# CarrierBoard_V7.net
KiCad netlist of a schematic drawn in EAGLE
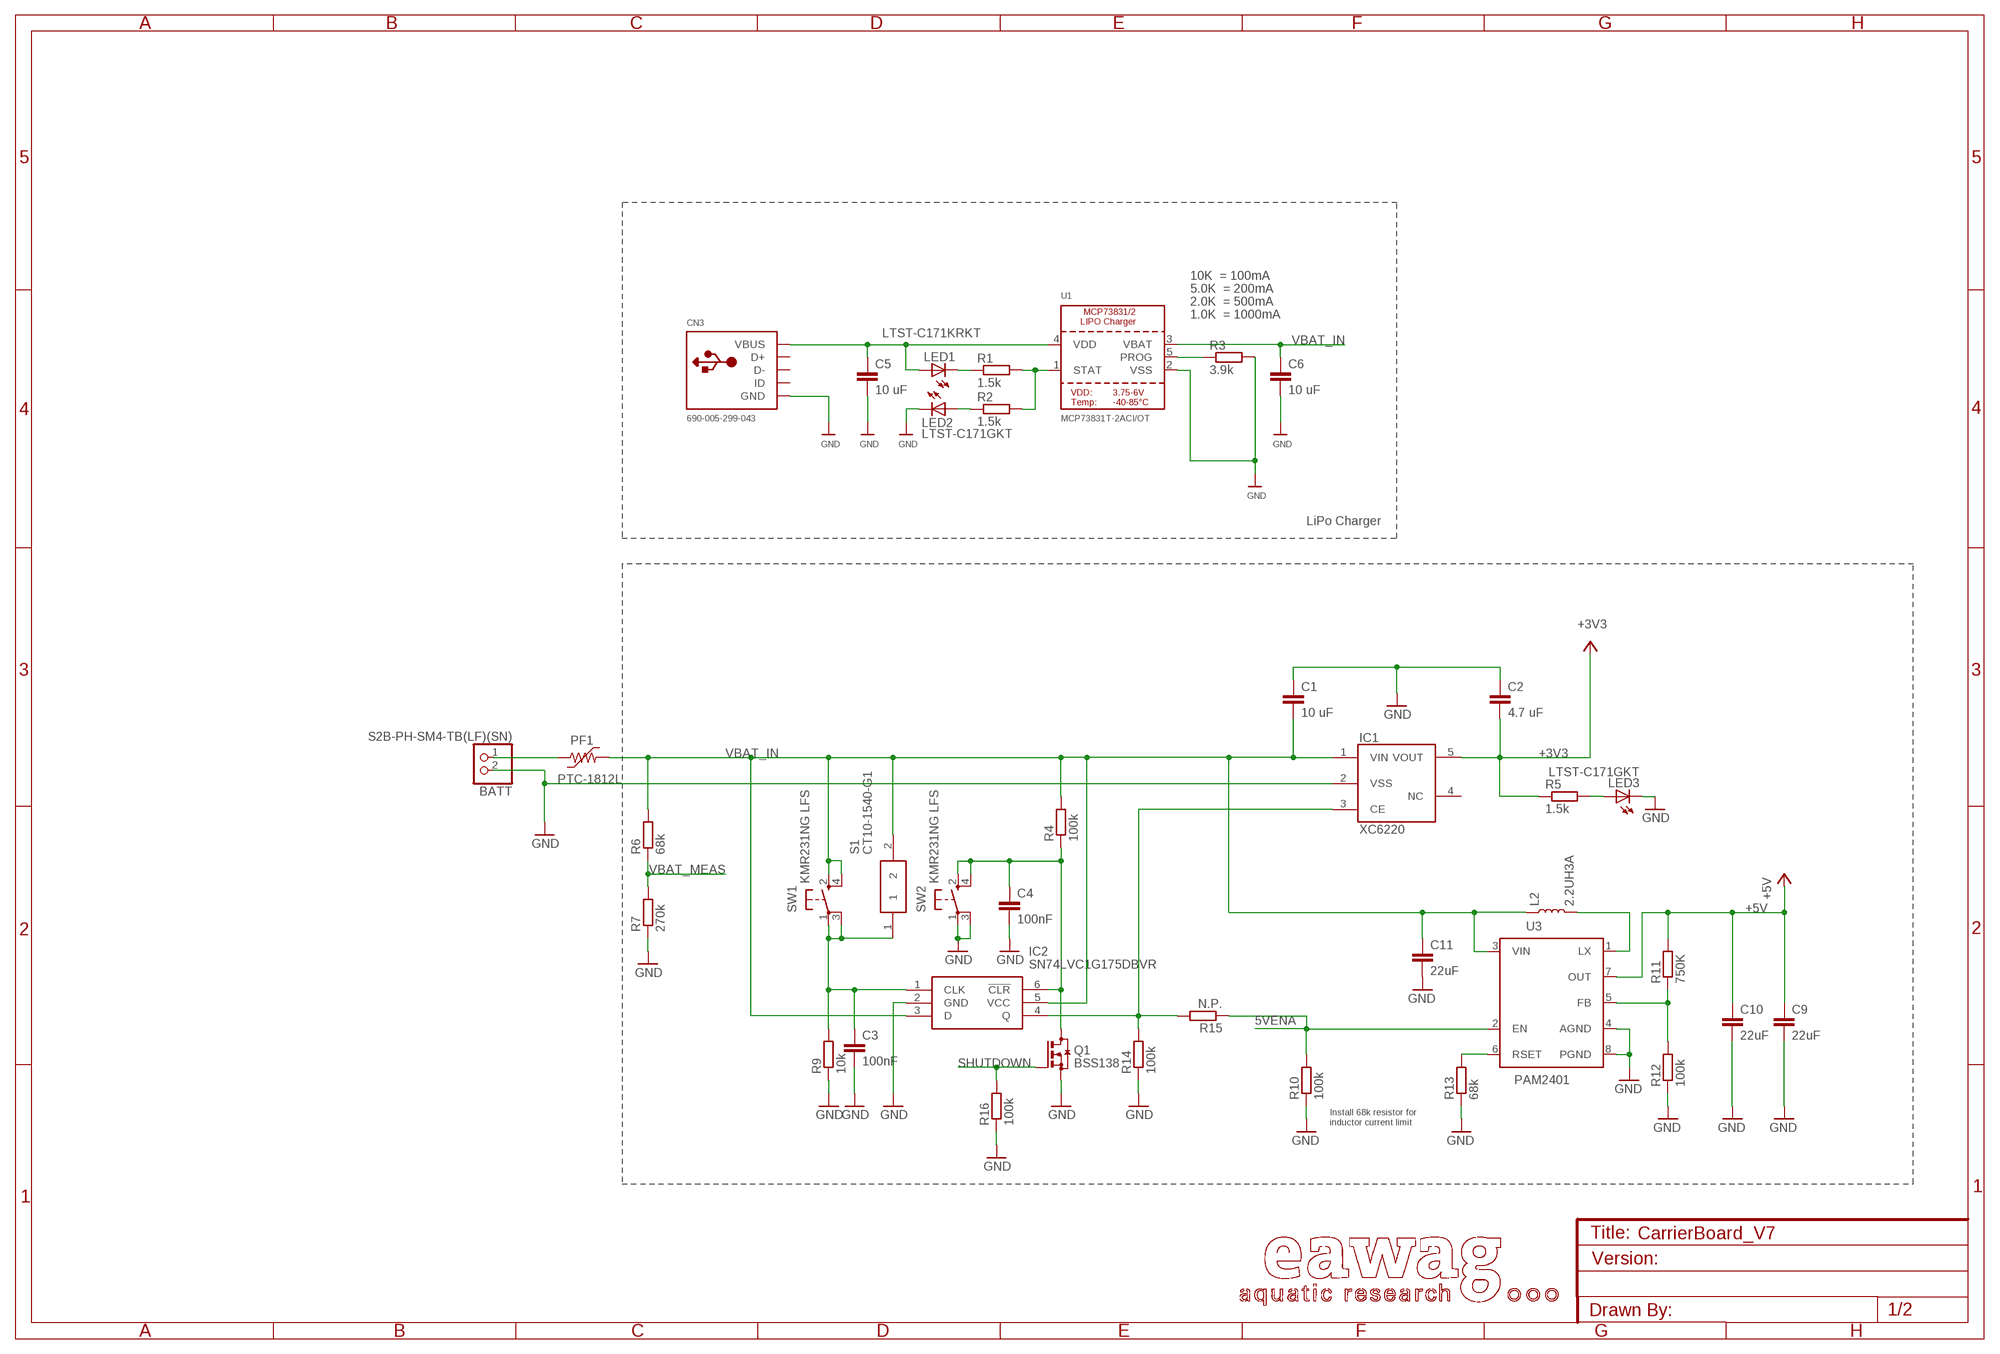
[diagram p0: schematic, sheet 1]
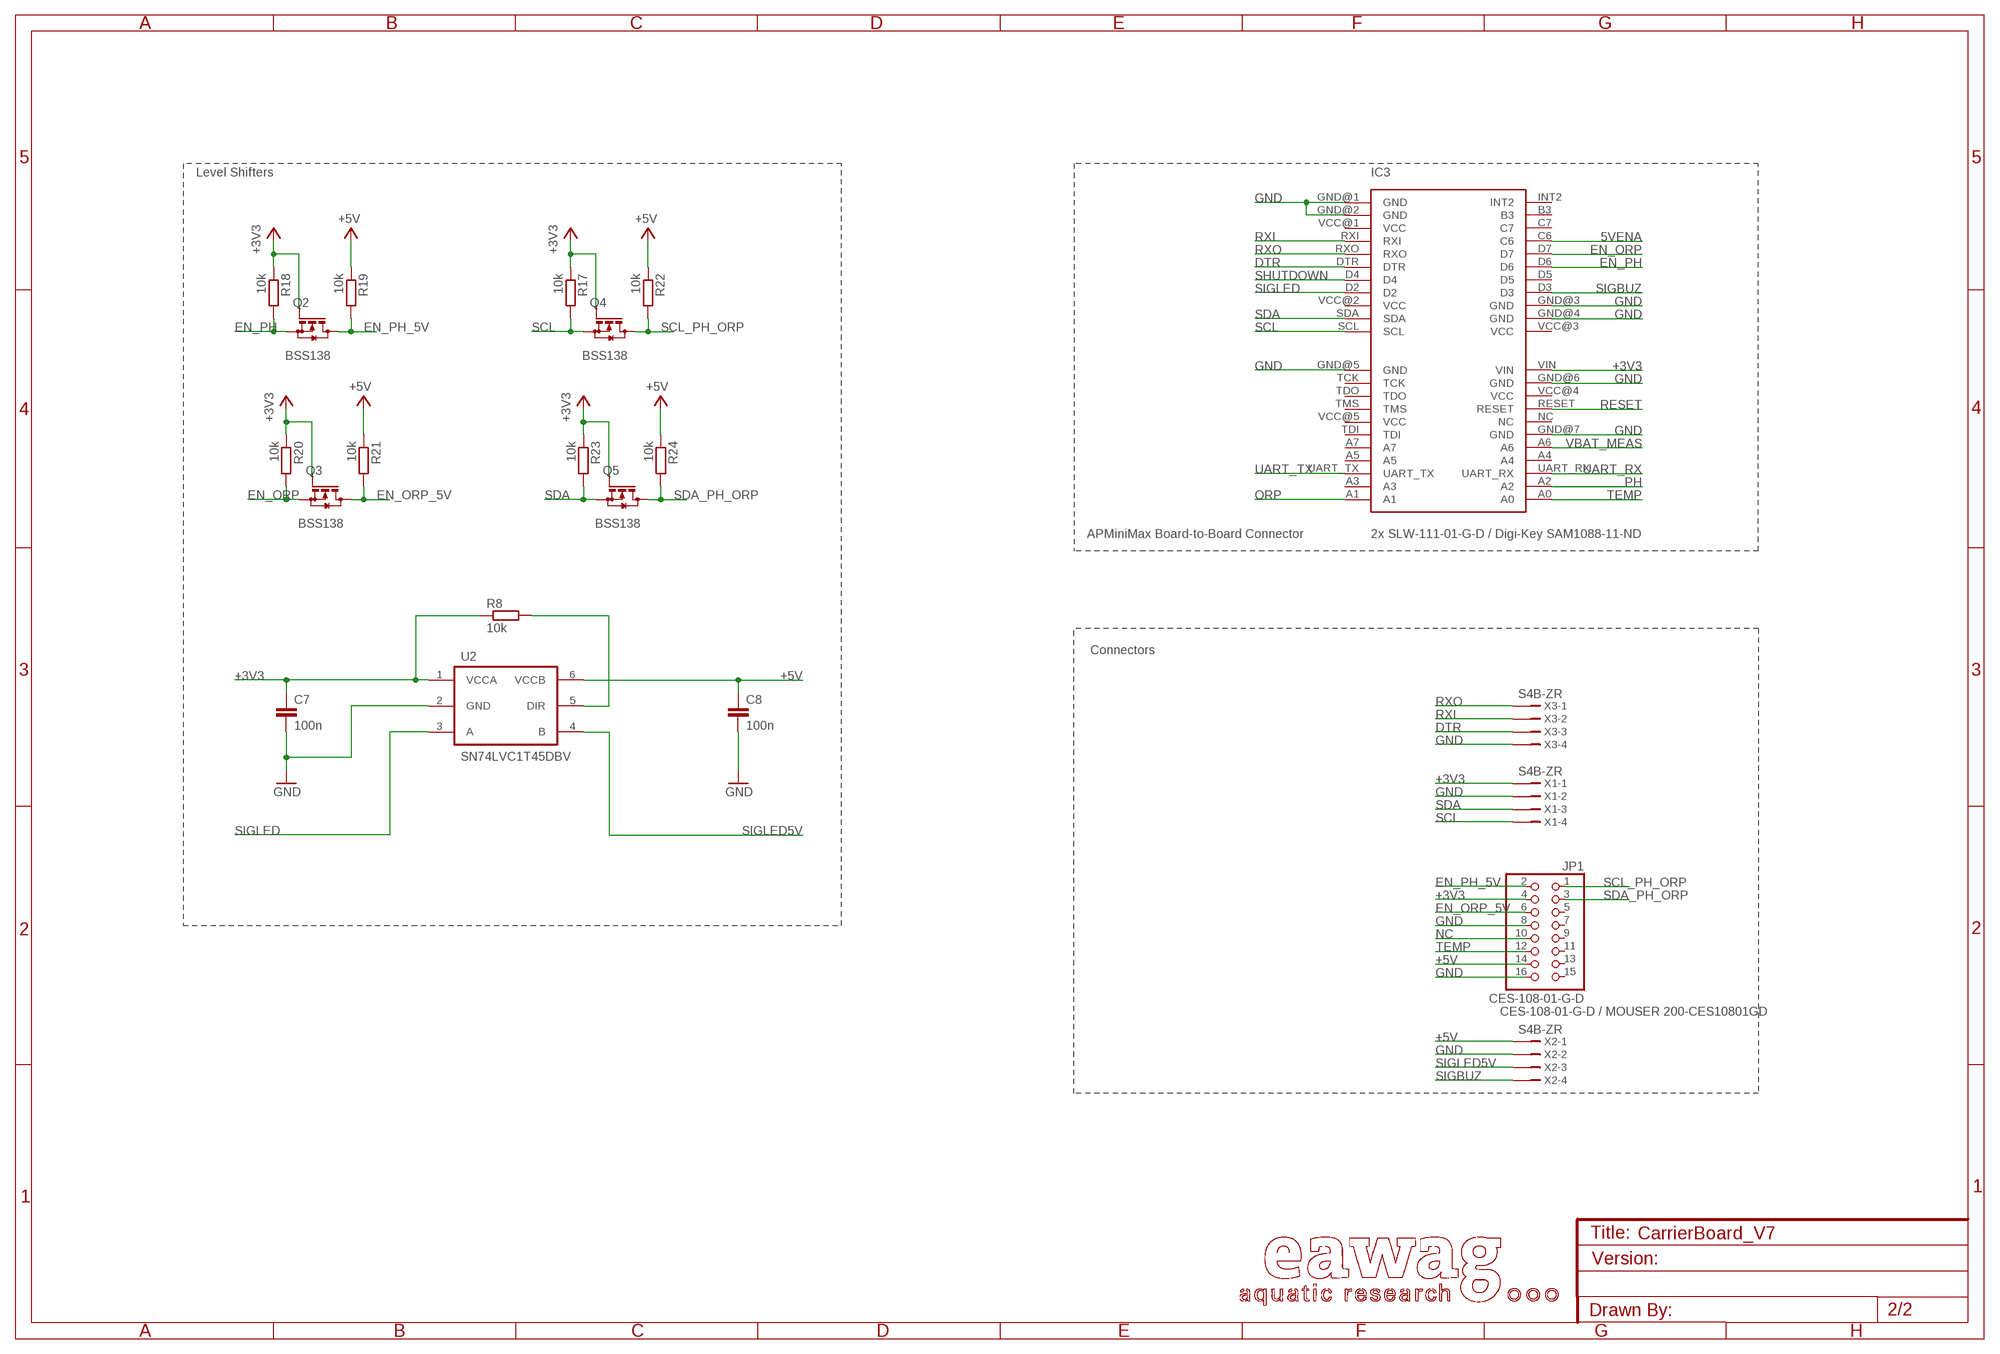
[diagram p1: schematic, sheet 2]

(export (version "E")
  (design (tool "Eeschema 10.0.6"))
  (components
    (comp (ref "C7")
      (value "100n")
      (footprint "eagle-import:C0805")
      (libsource (lib "eagle-import") (part "rcl_C-EUC0805"))
    )
    (comp (ref "C8")
      (value "100n")
      (footprint "eagle-import:C0805")
      (libsource (lib "eagle-import") (part "rcl_C-EUC0805"))
    )
    (comp (ref "IC3")
      (value "SLW-111-01-G-D")
      (footprint "eagle-import:APE")
      (libsource (lib "eagle-import") (part "APE"))
    )
    (comp (ref "JP1")
      (value "CES-108-01-G-D")
      (footprint "eagle-import:2X08")
      (libsource (lib "eagle-import") (part "PINHD-2X8"))
    )
    (comp (ref "Q2")
      (value "BSS138")
      (footprint "eagle-import:SOT23")
      (libsource (lib "eagle-import") (part "BSS138"))
    )
    (comp (ref "Q3")
      (value "BSS138")
      (footprint "eagle-import:SOT23")
      (libsource (lib "eagle-import") (part "BSS138"))
    )
    (comp (ref "Q4")
      (value "BSS138")
      (footprint "eagle-import:SOT23")
      (libsource (lib "eagle-import") (part "BSS138"))
    )
    (comp (ref "Q5")
      (value "BSS138")
      (footprint "eagle-import:SOT23")
      (libsource (lib "eagle-import") (part "BSS138"))
    )
    (comp (ref "R8")
      (value "10k")
      (footprint "eagle-import:R0603")
      (libsource (lib "eagle-import") (part "rcl_R-EU_R0603"))
    )
    (comp (ref "R17")
      (value "10k")
      (footprint "eagle-import:R0603")
      (libsource (lib "eagle-import") (part "R-EU_R0603"))
    )
    (comp (ref "R18")
      (value "10k")
      (footprint "eagle-import:R0603")
      (libsource (lib "eagle-import") (part "R-EU_R0603"))
    )
    (comp (ref "R19")
      (value "10k")
      (footprint "eagle-import:R0603")
      (libsource (lib "eagle-import") (part "R-EU_R0603"))
    )
    (comp (ref "R20")
      (value "10k")
      (footprint "eagle-import:R0603")
      (libsource (lib "eagle-import") (part "R-EU_R0603"))
    )
    (comp (ref "R21")
      (value "10k")
      (footprint "eagle-import:R0603")
      (libsource (lib "eagle-import") (part "R-EU_R0603"))
    )
    (comp (ref "R22")
      (value "10k")
      (footprint "eagle-import:R0603")
      (libsource (lib "eagle-import") (part "R-EU_R0603"))
    )
    (comp (ref "R23")
      (value "10k")
      (footprint "eagle-import:R0603")
      (libsource (lib "eagle-import") (part "R-EU_R0603"))
    )
    (comp (ref "R24")
      (value "10k")
      (footprint "eagle-import:R0603")
      (libsource (lib "eagle-import") (part "R-EU_R0603"))
    )
    (comp (ref "U2")
      (value "SN74LVC1T45DBV")
      (footprint "eagle-import:SOT23-6")
      (libsource (lib "eagle-import") (part "SN74LVC1T45DBV"))
    )
    (comp (ref "X1")
      (value "S4B-ZR")
      (footprint "eagle-import:S4B-ZR")
      (fields (field (name "MF") "FARNELL") (field (name "MPN") "S4B-ZR(LF)(SN)"))
      (libsource (lib "eagle-import") (part "?4B-ZRS"))
    )
    (comp (ref "X2")
      (value "S4B-ZR")
      (footprint "eagle-import:S4B-ZR")
      (fields (field (name "MF") "FARNELL") (field (name "MPN") "S4B-ZR(LF)(SN)"))
      (libsource (lib "eagle-import") (part "?4B-ZRS"))
    )
    (comp (ref "X3")
      (value "S4B-ZR")
      (footprint "eagle-import:S4B-ZR")
      (fields (field (name "MF") "FARNELL") (field (name "MPN") "S4B-ZR(LF)(SN)"))
      (libsource (lib "eagle-import") (part "?4B-ZRS"))
    )
    (comp (ref "BATT")
      (value "S2B-PH-SM4-TB(LF)(SN)")
      (footprint "eagle-import:JST-PH-2-SMT-RA")
      (libsource (lib "eagle-import") (part "JST_2PIN-SMT-RA"))
    )
    (comp (ref "C1")
      (value "10 uF")
      (footprint "eagle-import:C1206")
      (libsource (lib "eagle-import") (part "rcl_C-EUC1206"))
    )
    (comp (ref "C2")
      (value "4.7 uF")
      (footprint "eagle-import:C1206")
      (libsource (lib "eagle-import") (part "rcl_C-EUC1206"))
    )
    (comp (ref "C3")
      (value "100nF")
      (footprint "eagle-import:C0603")
      (libsource (lib "eagle-import") (part "C-EUC0603"))
    )
    (comp (ref "C4")
      (value "100nF")
      (footprint "eagle-import:C0603")
      (libsource (lib "eagle-import") (part "C-EUC0603"))
    )
    (comp (ref "C5")
      (value "10 uF")
      (footprint "eagle-import:C1206")
      (libsource (lib "eagle-import") (part "rcl_C-EUC1206"))
    )
    (comp (ref "C6")
      (value "10 uF")
      (footprint "eagle-import:C1206")
      (libsource (lib "eagle-import") (part "rcl_C-EUC1206"))
    )
    (comp (ref "C9")
      (value "22uF")
      (footprint "eagle-import:C0805")
      (libsource (lib "eagle-import") (part "C-EUC0805"))
    )
    (comp (ref "C10")
      (value "22uF")
      (footprint "eagle-import:C0805")
      (libsource (lib "eagle-import") (part "C-EUC0805"))
    )
    (comp (ref "C11")
      (value "22uF")
      (footprint "eagle-import:C0805")
      (libsource (lib "eagle-import") (part "C-EUC0805"))
    )
    (comp (ref "CN3")
      (value "690-005-299-043")
      (footprint "eagle-import:USB-MINIB")
      (libsource (lib "eagle-import") (part "USBMINIB"))
    )
    (comp (ref "IC1")
      (value "XC6220SOT-25")
      (footprint "eagle-import:SOT25")
      (libsource (lib "eagle-import") (part "XC6220SOT-25"))
    )
    (comp (ref "IC2")
      (value "SN74LVC1G175DBVR")
      (footprint "eagle-import:SOT95P280X145-6N")
      (fields (field (name "MOUSER_PART_NUMBER") "595-SN74LVC1G175DBVR"))
      (libsource (lib "eagle-import") (part "SN74LVC1G175DBVR"))
    )
    (comp (ref "L2")
      (value "2.2UH3A")
      (footprint "eagle-import:INDUCTOR_4X4MM")
      (libsource (lib "eagle-import") (part "INDUCTOR-IFSC1515AHER2R2M01"))
    )
    (comp (ref "LED1")
      (value "LTST-C171KRKT")
      (footprint "eagle-import:CHIPLED_0805")
      (libsource (lib "eagle-import") (part "LEDCHIPLED_0805"))
    )
    (comp (ref "LED2")
      (value "LTST-C171GKT")
      (footprint "eagle-import:CHIPLED_0805")
      (libsource (lib "eagle-import") (part "LEDCHIPLED_0805"))
    )
    (comp (ref "LED3")
      (value "LTST-C171GKT")
      (footprint "eagle-import:CHIPLED_0805")
      (libsource (lib "eagle-import") (part "eawag_LEDCHIPLED_0805"))
    )
    (comp (ref "PF1")
      (value "PTC-1812L")
      (footprint "eagle-import:1812L")
      (libsource (lib "eagle-import") (part "PTC-1812L"))
    )
    (comp (ref "Q1")
      (value "BSS138")
      (footprint "eagle-import:SOT23")
      (libsource (lib "eagle-import") (part "BSS138"))
    )
    (comp (ref "R1")
      (value "1.5k")
      (footprint "eagle-import:R0603")
      (libsource (lib "eagle-import") (part "R-EU_R0603"))
    )
    (comp (ref "R2")
      (value "1.5k")
      (footprint "eagle-import:R0603")
      (libsource (lib "eagle-import") (part "R-EU_R0603"))
    )
    (comp (ref "R3")
      (value "3.9k")
      (footprint "eagle-import:R0603")
      (libsource (lib "eagle-import") (part "R-EU_R0603"))
    )
    (comp (ref "R4")
      (value "100k")
      (footprint "eagle-import:R0603")
      (libsource (lib "eagle-import") (part "R-EU_R0603"))
    )
    (comp (ref "R5")
      (value "1.5k")
      (footprint "eagle-import:R0603")
      (libsource (lib "eagle-import") (part "rcl_R-EU_R0603"))
    )
    (comp (ref "R6")
      (value "68k")
      (footprint "eagle-import:R0603")
      (libsource (lib "eagle-import") (part "R-EU_R0603"))
    )
    (comp (ref "R7")
      (value "270k")
      (footprint "eagle-import:R0603")
      (libsource (lib "eagle-import") (part "rcl_R-EU_R0603"))
    )
    (comp (ref "R9")
      (value "10k")
      (footprint "eagle-import:R0603")
      (libsource (lib "eagle-import") (part "R-EU_R0603"))
    )
    (comp (ref "R10")
      (value "100k")
      (footprint "eagle-import:R0603")
      (libsource (lib "eagle-import") (part "R-EU_R0603"))
    )
    (comp (ref "R11")
      (value "750K")
      (footprint "eagle-import:R0603")
      (libsource (lib "eagle-import") (part "R-EU_R0603"))
    )
    (comp (ref "R12")
      (value "100k")
      (footprint "eagle-import:R0603")
      (libsource (lib "eagle-import") (part "R-EU_R0603"))
    )
    (comp (ref "R13")
      (value "68k")
      (footprint "eagle-import:R0603")
      (libsource (lib "eagle-import") (part "R-EU_R0603"))
    )
    (comp (ref "R14")
      (value "100k")
      (footprint "eagle-import:R0603")
      (libsource (lib "eagle-import") (part "R-EU_R0603"))
    )
    (comp (ref "R15")
      (value "N.P.")
      (footprint "eagle-import:R0603")
      (libsource (lib "eagle-import") (part "R-EU_R0603"))
    )
    (comp (ref "R16")
      (value "100k")
      (footprint "eagle-import:R0603")
      (libsource (lib "eagle-import") (part "R-EU_R0603"))
    )
    (comp (ref "S1")
      (value "CT10-1540-G1")
      (footprint "eagle-import:CT101540G1")
      (fields (field (name "MOUSER_PART_NUMBER") "816-CT10-1540-G1"))
      (libsource (lib "eagle-import") (part "CT10-1540-G1"))
    )
    (comp (ref "SW1")
      (value "KMR231NG LFS")
      (footprint "eagle-import:KMR2")
      (libsource (lib "eagle-import") (part "SPST_TACT-KMR2"))
    )
    (comp (ref "SW2")
      (value "KMR231NG LFS")
      (footprint "eagle-import:KMR2")
      (libsource (lib "eagle-import") (part "SPST_TACT-KMR2"))
    )
    (comp (ref "U1")
      (value "MCP73831T-2ACI/OT")
      (footprint "eagle-import:SOT23-5")
      (libsource (lib "eagle-import") (part "MCP73831/2"))
    )
    (comp (ref "U3")
      (value "PAM2401")
      (footprint "eagle-import:MSOP8")
      (libsource (lib "eagle-import") (part "PAM2401"))
    )
  )
  (nets
    (net (code "1") (name "+3V3") (class "Default")
      (node (ref "C2") (pin "2") (pinfunction "2_2") (pintype "passive"))
      (node (ref "C7") (pin "1") (pinfunction "1_1") (pintype "passive"))
      (node (ref "IC1") (pin "5") (pinfunction "VOUT_5") (pintype "power_in"))
      (node (ref "IC3") (pin "VIN") (pinfunction "VIN_VIN") (pintype "bidirectional"))
      (node (ref "JP1") (pin "4") (pinfunction "4_4") (pintype "passive"))
      (node (ref "Q2") (pin "1") (pinfunction "G_1") (pintype "passive"))
      (node (ref "Q3") (pin "1") (pinfunction "G_1") (pintype "passive"))
      (node (ref "Q4") (pin "1") (pinfunction "G_1") (pintype "passive"))
      (node (ref "Q5") (pin "1") (pinfunction "G_1") (pintype "passive"))
      (node (ref "R17") (pin "1") (pinfunction "1_1") (pintype "passive"))
      (node (ref "R18") (pin "1") (pinfunction "1_1") (pintype "passive"))
      (node (ref "R20") (pin "1") (pinfunction "1_1") (pintype "passive"))
      (node (ref "R23") (pin "1") (pinfunction "1_1") (pintype "passive"))
      (node (ref "R5") (pin "1") (pinfunction "1_1") (pintype "passive"))
      (node (ref "R8") (pin "1") (pinfunction "1_1") (pintype "passive"))
      (node (ref "U2") (pin "1") (pinfunction "VCCA_1") (pintype "power_in"))
      (node (ref "X1") (pin "1") (pinfunction "1_1") (pintype "passive"))
    )
    (net (code "2") (name "+5V") (class "Default")
      (node (ref "C10") (pin "1") (pinfunction "1_1") (pintype "passive"))
      (node (ref "C8") (pin "1") (pinfunction "1_1") (pintype "passive"))
      (node (ref "C9") (pin "1") (pinfunction "1_1") (pintype "passive"))
      (node (ref "JP1") (pin "14") (pinfunction "14_14") (pintype "passive"))
      (node (ref "R11") (pin "2") (pinfunction "2_2") (pintype "passive"))
      (node (ref "R19") (pin "1") (pinfunction "1_1") (pintype "passive"))
      (node (ref "R21") (pin "1") (pinfunction "1_1") (pintype "passive"))
      (node (ref "R22") (pin "1") (pinfunction "1_1") (pintype "passive"))
      (node (ref "R24") (pin "1") (pinfunction "1_1") (pintype "passive"))
      (node (ref "U2") (pin "6") (pinfunction "VCCB_6") (pintype "power_in"))
      (node (ref "U3") (pin "7") (pinfunction "OUT_7") (pintype "bidirectional"))
      (node (ref "X2") (pin "1") (pinfunction "1_1") (pintype "passive"))
    )
    (net (code "3") (name "5VENA") (class "Default")
      (node (ref "IC3") (pin "C6") (pinfunction "C6_C6") (pintype "bidirectional"))
      (node (ref "R10") (pin "2") (pinfunction "2_2") (pintype "passive"))
      (node (ref "R15") (pin "1") (pinfunction "1_1") (pintype "passive"))
      (node (ref "U3") (pin "2") (pinfunction "EN_2") (pintype "bidirectional"))
    )
    (net (code "4") (name "DTR") (class "Default")
      (node (ref "IC3") (pin "DTR") (pinfunction "DTR_DTR") (pintype "bidirectional"))
      (node (ref "X3") (pin "3") (pinfunction "1_3") (pintype "passive"))
    )
    (net (code "5") (name "EN_ORP") (class "Default")
      (node (ref "IC3") (pin "D7") (pinfunction "D7_D7") (pintype "bidirectional"))
      (node (ref "Q3") (pin "2") (pinfunction "S_2") (pintype "passive"))
      (node (ref "R20") (pin "2") (pinfunction "2_2") (pintype "passive"))
    )
    (net (code "6") (name "EN_ORP_5V") (class "Default")
      (node (ref "JP1") (pin "6") (pinfunction "6_6") (pintype "passive"))
      (node (ref "Q3") (pin "3") (pinfunction "D_3") (pintype "passive"))
      (node (ref "R21") (pin "2") (pinfunction "2_2") (pintype "passive"))
    )
    (net (code "7") (name "EN_PH") (class "Default")
      (node (ref "IC3") (pin "D6") (pinfunction "D6_D6") (pintype "bidirectional"))
      (node (ref "Q2") (pin "2") (pinfunction "S_2") (pintype "passive"))
      (node (ref "R18") (pin "2") (pinfunction "2_2") (pintype "passive"))
    )
    (net (code "8") (name "EN_PH_5V") (class "Default")
      (node (ref "JP1") (pin "2") (pinfunction "2_2") (pintype "passive"))
      (node (ref "Q2") (pin "3") (pinfunction "D_3") (pintype "passive"))
      (node (ref "R19") (pin "2") (pinfunction "2_2") (pintype "passive"))
    )
    (net (code "9") (name "GND") (class "Default")
      (node (ref "BATT") (pin "2") (pinfunction "1_2") (pintype "passive"))
      (node (ref "C1") (pin "1") (pinfunction "1_1") (pintype "passive"))
      (node (ref "C10") (pin "2") (pinfunction "2_2") (pintype "passive"))
      (node (ref "C11") (pin "2") (pinfunction "2_2") (pintype "passive"))
      (node (ref "C2") (pin "1") (pinfunction "1_1") (pintype "passive"))
      (node (ref "C3") (pin "2") (pinfunction "2_2") (pintype "passive"))
      (node (ref "C4") (pin "2") (pinfunction "2_2") (pintype "passive"))
      (node (ref "C5") (pin "2") (pinfunction "2_2") (pintype "passive"))
      (node (ref "C6") (pin "2") (pinfunction "2_2") (pintype "passive"))
      (node (ref "C7") (pin "2") (pinfunction "2_2") (pintype "passive"))
      (node (ref "C8") (pin "2") (pinfunction "2_2") (pintype "passive"))
      (node (ref "C9") (pin "2") (pinfunction "2_2") (pintype "passive"))
      (node (ref "CN3") (pin "GND") (pinfunction "GND_GND") (pintype "power_in"))
      (node (ref "IC1") (pin "2") (pinfunction "VSS_2") (pintype "power_in"))
      (node (ref "IC2") (pin "2") (pinfunction "GND_2") (pintype "power_in"))
      (node (ref "IC3") (pin "GND@1") (pinfunction "GND_GND@1") (pintype "bidirectional"))
      (node (ref "IC3") (pin "GND@2") (pinfunction "GND_GND@2") (pintype "bidirectional"))
      (node (ref "IC3") (pin "GND@3") (pinfunction "GND_GND@3") (pintype "bidirectional"))
      (node (ref "IC3") (pin "GND@4") (pinfunction "GND_GND@4") (pintype "bidirectional"))
      (node (ref "IC3") (pin "GND@5") (pinfunction "GND_GND@5") (pintype "bidirectional"))
      (node (ref "IC3") (pin "GND@6") (pinfunction "GND_GND@6") (pintype "bidirectional"))
      (node (ref "IC3") (pin "GND@7") (pinfunction "GND_GND@7") (pintype "bidirectional"))
      (node (ref "JP1") (pin "16") (pinfunction "16_16") (pintype "passive"))
      (node (ref "JP1") (pin "8") (pinfunction "8_8") (pintype "passive"))
      (node (ref "LED2") (pin "C") (pinfunction "C_C") (pintype "passive"))
      (node (ref "LED3") (pin "C") (pinfunction "C_C") (pintype "passive"))
      (node (ref "Q1") (pin "2") (pinfunction "S_2") (pintype "passive"))
      (node (ref "R10") (pin "1") (pinfunction "1_1") (pintype "passive"))
      (node (ref "R12") (pin "1") (pinfunction "1_1") (pintype "passive"))
      (node (ref "R13") (pin "1") (pinfunction "1_1") (pintype "passive"))
      (node (ref "R14") (pin "1") (pinfunction "1_1") (pintype "passive"))
      (node (ref "R16") (pin "1") (pinfunction "1_1") (pintype "passive"))
      (node (ref "R3") (pin "2") (pinfunction "2_2") (pintype "passive"))
      (node (ref "R7") (pin "1") (pinfunction "1_1") (pintype "passive"))
      (node (ref "R9") (pin "1") (pinfunction "1_1") (pintype "passive"))
      (node (ref "SW2") (pin "1") (pinfunction "P_1") (pintype "passive"))
      (node (ref "SW2") (pin "3") (pinfunction "P1_3") (pintype "passive"))
      (node (ref "U1") (pin "2") (pinfunction "VSS_2") (pintype "power_in"))
      (node (ref "U2") (pin "2") (pinfunction "GND_2") (pintype "power_in"))
      (node (ref "U3") (pin "4") (pinfunction "AGND_4") (pintype "bidirectional"))
      (node (ref "U3") (pin "8") (pinfunction "PGND_8") (pintype "bidirectional"))
      (node (ref "X1") (pin "2") (pinfunction "1_2") (pintype "passive"))
      (node (ref "X2") (pin "2") (pinfunction "1_2") (pintype "passive"))
      (node (ref "X3") (pin "4") (pinfunction "1_4") (pintype "passive"))
    )
    (net (code "10") (name "NC") (class "Default")
      (node (ref "JP1") (pin "10") (pinfunction "10_10") (pintype "passive"))
    )
    (net (code "11") (name "Net-(BATT-2)") (class "Default")
      (node (ref "BATT") (pin "1") (pinfunction "2_1") (pintype "passive"))
      (node (ref "PF1") (pin "1") (pinfunction "1_1") (pintype "passive"))
    )
    (net (code "12") (name "Net-(IC1-CE)") (class "Default")
      (node (ref "IC1") (pin "3") (pinfunction "CE_3") (pintype "input"))
      (node (ref "IC2") (pin "4") (pinfunction "Q_4") (pintype "bidirectional"))
      (node (ref "R14") (pin "2") (pinfunction "2_2") (pintype "passive"))
      (node (ref "R15") (pin "2") (pinfunction "2_2") (pintype "passive"))
    )
    (net (code "13") (name "Net-(IC2-CLK)") (class "Default")
      (node (ref "C3") (pin "1") (pinfunction "1_1") (pintype "passive"))
      (node (ref "IC2") (pin "1") (pinfunction "CLK_1") (pintype "input"))
      (node (ref "R9") (pin "2") (pinfunction "2_2") (pintype "passive"))
      (node (ref "S1") (pin "1") (pinfunction "1_1") (pintype "bidirectional"))
      (node (ref "SW1") (pin "1") (pinfunction "P_1") (pintype "passive"))
      (node (ref "SW1") (pin "3") (pinfunction "P1_3") (pintype "passive"))
    )
    (net (code "14") (name "Net-(IC2-~{CLR})") (class "Default")
      (node (ref "C4") (pin "1") (pinfunction "1_1") (pintype "passive"))
      (node (ref "IC2") (pin "6") (pinfunction "~{CLR}_6") (pintype "bidirectional"))
      (node (ref "Q1") (pin "3") (pinfunction "D_3") (pintype "passive"))
      (node (ref "R4") (pin "1") (pinfunction "1_1") (pintype "passive"))
      (node (ref "SW2") (pin "2") (pinfunction "S_2") (pintype "passive"))
      (node (ref "SW2") (pin "4") (pinfunction "S1_4") (pintype "passive"))
    )
    (net (code "15") (name "Net-(L2-2)") (class "Default")
      (node (ref "L2") (pin "P$2") (pinfunction "2_P$2") (pintype "passive"))
      (node (ref "U3") (pin "1") (pinfunction "LX_1") (pintype "bidirectional"))
    )
    (net (code "16") (name "Net-(LED1-PadC)") (class "Default")
      (node (ref "LED1") (pin "C") (pinfunction "C_C") (pintype "passive"))
      (node (ref "R1") (pin "1") (pinfunction "1_1") (pintype "passive"))
    )
    (net (code "17") (name "Net-(LED2-PadA)") (class "Default")
      (node (ref "LED2") (pin "A") (pinfunction "A_A") (pintype "passive"))
      (node (ref "R2") (pin "1") (pinfunction "1_1") (pintype "passive"))
    )
    (net (code "18") (name "Net-(LED3-PadA)") (class "Default")
      (node (ref "LED3") (pin "A") (pinfunction "A_A") (pintype "passive"))
      (node (ref "R5") (pin "2") (pinfunction "2_2") (pintype "passive"))
    )
    (net (code "19") (name "Net-(U1-PROG)") (class "Default")
      (node (ref "R3") (pin "1") (pinfunction "1_1") (pintype "passive"))
      (node (ref "U1") (pin "5") (pinfunction "PROG_5") (pintype "input"))
    )
    (net (code "20") (name "Net-(U1-STAT)") (class "Default")
      (node (ref "R1") (pin "2") (pinfunction "2_2") (pintype "passive"))
      (node (ref "R2") (pin "2") (pinfunction "2_2") (pintype "passive"))
      (node (ref "U1") (pin "1") (pinfunction "STAT_1") (pintype "output"))
    )
    (net (code "21") (name "Net-(U1-VDD)") (class "Default")
      (node (ref "C5") (pin "1") (pinfunction "1_1") (pintype "passive"))
      (node (ref "CN3") (pin "VBUS") (pinfunction "VBUS_VBUS") (pintype "power_in"))
      (node (ref "LED1") (pin "A") (pinfunction "A_A") (pintype "passive"))
      (node (ref "U1") (pin "4") (pinfunction "VDD_4") (pintype "power_in"))
    )
    (net (code "22") (name "Net-(U2-DIR)") (class "Default")
      (node (ref "R8") (pin "2") (pinfunction "2_2") (pintype "passive"))
      (node (ref "U2") (pin "5") (pinfunction "DIR_5") (pintype "input"))
    )
    (net (code "23") (name "Net-(U3-FB)") (class "Default")
      (node (ref "R11") (pin "1") (pinfunction "1_1") (pintype "passive"))
      (node (ref "R12") (pin "2") (pinfunction "2_2") (pintype "passive"))
      (node (ref "U3") (pin "5") (pinfunction "FB_5") (pintype "bidirectional"))
    )
    (net (code "24") (name "Net-(U3-RSET)") (class "Default")
      (node (ref "R13") (pin "2") (pinfunction "2_2") (pintype "passive"))
      (node (ref "U3") (pin "6") (pinfunction "RSET_6") (pintype "bidirectional"))
    )
    (net (code "25") (name "ORP") (class "Default")
      (node (ref "IC3") (pin "A1") (pinfunction "A1_A1") (pintype "bidirectional"))
    )
    (net (code "26") (name "PH") (class "Default")
      (node (ref "IC3") (pin "A2") (pinfunction "A2_A2") (pintype "bidirectional"))
    )
    (net (code "27") (name "RESET") (class "Default")
      (node (ref "IC3") (pin "RESET") (pinfunction "RESET_RESET") (pintype "bidirectional"))
    )
    (net (code "28") (name "RXI") (class "Default")
      (node (ref "IC3") (pin "RXI") (pinfunction "RXI_RXI") (pintype "bidirectional"))
      (node (ref "X3") (pin "2") (pinfunction "1_2") (pintype "passive"))
    )
    (net (code "29") (name "RXO") (class "Default")
      (node (ref "IC3") (pin "RXO") (pinfunction "RXO_RXO") (pintype "bidirectional"))
      (node (ref "X3") (pin "1") (pinfunction "1_1") (pintype "passive"))
    )
    (net (code "30") (name "SCL") (class "Default")
      (node (ref "IC3") (pin "SCL") (pinfunction "SCL_SCL") (pintype "bidirectional"))
      (node (ref "Q4") (pin "2") (pinfunction "S_2") (pintype "passive"))
      (node (ref "R17") (pin "2") (pinfunction "2_2") (pintype "passive"))
      (node (ref "X1") (pin "4") (pinfunction "1_4") (pintype "passive"))
    )
    (net (code "31") (name "SCL_PH_ORP") (class "Default")
      (node (ref "JP1") (pin "1") (pinfunction "1_1") (pintype "passive"))
      (node (ref "Q4") (pin "3") (pinfunction "D_3") (pintype "passive"))
      (node (ref "R22") (pin "2") (pinfunction "2_2") (pintype "passive"))
    )
    (net (code "32") (name "SDA") (class "Default")
      (node (ref "IC3") (pin "SDA") (pinfunction "SDA_SDA") (pintype "bidirectional"))
      (node (ref "Q5") (pin "2") (pinfunction "S_2") (pintype "passive"))
      (node (ref "R23") (pin "2") (pinfunction "2_2") (pintype "passive"))
      (node (ref "X1") (pin "3") (pinfunction "1_3") (pintype "passive"))
    )
    (net (code "33") (name "SDA_PH_ORP") (class "Default")
      (node (ref "JP1") (pin "3") (pinfunction "3_3") (pintype "passive"))
      (node (ref "Q5") (pin "3") (pinfunction "D_3") (pintype "passive"))
      (node (ref "R24") (pin "2") (pinfunction "2_2") (pintype "passive"))
    )
    (net (code "34") (name "SHUTDOWN") (class "Default")
      (node (ref "IC3") (pin "D4") (pinfunction "D4_D4") (pintype "bidirectional"))
      (node (ref "Q1") (pin "1") (pinfunction "G_1") (pintype "passive"))
      (node (ref "R16") (pin "2") (pinfunction "2_2") (pintype "passive"))
    )
    (net (code "35") (name "SIGBUZ") (class "Default")
      (node (ref "IC3") (pin "D3") (pinfunction "D3_D3") (pintype "bidirectional"))
      (node (ref "X2") (pin "4") (pinfunction "1_4") (pintype "passive"))
    )
    (net (code "36") (name "SIGLED") (class "Default")
      (node (ref "IC3") (pin "D2") (pinfunction "D2_D2") (pintype "bidirectional"))
      (node (ref "U2") (pin "3") (pinfunction "A_3") (pintype "bidirectional"))
    )
    (net (code "37") (name "SIGLED5V") (class "Default")
      (node (ref "U2") (pin "4") (pinfunction "B_4") (pintype "bidirectional"))
      (node (ref "X2") (pin "3") (pinfunction "1_3") (pintype "passive"))
    )
    (net (code "38") (name "TEMP") (class "Default")
      (node (ref "IC3") (pin "A0") (pinfunction "A0_A0") (pintype "bidirectional"))
      (node (ref "JP1") (pin "12") (pinfunction "12_12") (pintype "passive"))
    )
    (net (code "39") (name "UART_RX") (class "Default")
      (node (ref "IC3") (pin "UART_RX") (pinfunction "UART_RX_UART_RX") (pintype "bidirectional"))
    )
    (net (code "40") (name "UART_TX") (class "Default")
      (node (ref "IC3") (pin "UART_TX") (pinfunction "UART_TX_UART_TX") (pintype "bidirectional"))
    )
    (net (code "41") (name "VBAT_IN") (class "Default")
      (node (ref "C1") (pin "2") (pinfunction "2_2") (pintype "passive"))
      (node (ref "C11") (pin "1") (pinfunction "1_1") (pintype "passive"))
      (node (ref "C6") (pin "1") (pinfunction "1_1") (pintype "passive"))
      (node (ref "IC1") (pin "1") (pinfunction "VIN_1") (pintype "power_in"))
      (node (ref "IC2") (pin "3") (pinfunction "D_3") (pintype "bidirectional"))
      (node (ref "IC2") (pin "5") (pinfunction "VCC_5") (pintype "power_in"))
      (node (ref "L2") (pin "P$1") (pinfunction "1_P$1") (pintype "passive"))
      (node (ref "PF1") (pin "2") (pinfunction "2_2") (pintype "passive"))
      (node (ref "R4") (pin "2") (pinfunction "2_2") (pintype "passive"))
      (node (ref "R6") (pin "2") (pinfunction "2_2") (pintype "passive"))
      (node (ref "S1") (pin "2") (pinfunction "2_2") (pintype "bidirectional"))
      (node (ref "SW1") (pin "2") (pinfunction "S_2") (pintype "passive"))
      (node (ref "SW1") (pin "4") (pinfunction "S1_4") (pintype "passive"))
      (node (ref "U1") (pin "3") (pinfunction "VBAT_3") (pintype "power_in"))
      (node (ref "U3") (pin "3") (pinfunction "VIN_3") (pintype "bidirectional"))
    )
    (net (code "42") (name "VBAT_MEAS") (class "Default")
      (node (ref "IC3") (pin "A6") (pinfunction "A6_A6") (pintype "bidirectional"))
      (node (ref "R6") (pin "1") (pinfunction "1_1") (pintype "passive"))
      (node (ref "R7") (pin "2") (pinfunction "2_2") (pintype "passive"))
    )
    (net (code "43") (name "unconnected-(CN3-PadD+)") (class "Default")
      (node (ref "CN3") (pin "D+") (pinfunction "D+_D+") (pintype "bidirectional"))
    )
    (net (code "44") (name "unconnected-(CN3-PadD-)") (class "Default")
      (node (ref "CN3") (pin "D-") (pinfunction "D-_D-") (pintype "bidirectional"))
    )
    (net (code "45") (name "unconnected-(CN3-PadID)") (class "Default")
      (node (ref "CN3") (pin "ID") (pinfunction "ID_ID") (pintype "bidirectional"))
    )
    (net (code "46") (name "unconnected-(IC1-NC-Pad4)") (class "Default")
      (node (ref "IC1") (pin "4") (pinfunction "NC_4") (pintype "no_connect"))
    )
    (net (code "47") (name "unconnected-(IC3-PadA3)") (class "Default")
      (node (ref "IC3") (pin "A3") (pinfunction "A3_A3") (pintype "bidirectional"))
    )
    (net (code "48") (name "unconnected-(IC3-PadA4)") (class "Default")
      (node (ref "IC3") (pin "A4") (pinfunction "A4_A4") (pintype "bidirectional"))
    )
    (net (code "49") (name "unconnected-(IC3-PadA5)") (class "Default")
      (node (ref "IC3") (pin "A5") (pinfunction "A5_A5") (pintype "bidirectional"))
    )
    (net (code "50") (name "unconnected-(IC3-PadA7)") (class "Default")
      (node (ref "IC3") (pin "A7") (pinfunction "A7_A7") (pintype "bidirectional"))
    )
    (net (code "51") (name "unconnected-(IC3-PadB3)") (class "Default")
      (node (ref "IC3") (pin "B3") (pinfunction "B3_B3") (pintype "bidirectional"))
    )
    (net (code "52") (name "unconnected-(IC3-PadC7)") (class "Default")
      (node (ref "IC3") (pin "C7") (pinfunction "C7_C7") (pintype "bidirectional"))
    )
    (net (code "53") (name "unconnected-(IC3-PadD5)") (class "Default")
      (node (ref "IC3") (pin "D5") (pinfunction "D5_D5") (pintype "bidirectional"))
    )
    (net (code "54") (name "unconnected-(IC3-PadINT2)") (class "Default")
      (node (ref "IC3") (pin "INT2") (pinfunction "INT2_INT2") (pintype "bidirectional"))
    )
    (net (code "55") (name "unconnected-(IC3-PadNC)") (class "Default")
      (node (ref "IC3") (pin "NC") (pinfunction "NC_NC") (pintype "bidirectional"))
    )
    (net (code "56") (name "unconnected-(IC3-PadTCK)") (class "Default")
      (node (ref "IC3") (pin "TCK") (pinfunction "TCK_TCK") (pintype "bidirectional"))
    )
    (net (code "57") (name "unconnected-(IC3-PadTDI)") (class "Default")
      (node (ref "IC3") (pin "TDI") (pinfunction "TDI_TDI") (pintype "bidirectional"))
    )
    (net (code "58") (name "unconnected-(IC3-PadTDO)") (class "Default")
      (node (ref "IC3") (pin "TDO") (pinfunction "TDO_TDO") (pintype "bidirectional"))
    )
    (net (code "59") (name "unconnected-(IC3-PadTMS)") (class "Default")
      (node (ref "IC3") (pin "TMS") (pinfunction "TMS_TMS") (pintype "bidirectional"))
    )
    (net (code "60") (name "unconnected-(IC3-VCC-PadVCC@1)") (class "Default")
      (node (ref "IC3") (pin "VCC@1") (pinfunction "VCC_VCC@1") (pintype "bidirectional"))
    )
    (net (code "61") (name "unconnected-(IC3-VCC-PadVCC@2)") (class "Default")
      (node (ref "IC3") (pin "VCC@2") (pinfunction "VCC_VCC@2") (pintype "bidirectional"))
    )
    (net (code "62") (name "unconnected-(IC3-VCC-PadVCC@3)") (class "Default")
      (node (ref "IC3") (pin "VCC@3") (pinfunction "VCC_VCC@3") (pintype "bidirectional"))
    )
    (net (code "63") (name "unconnected-(IC3-VCC-PadVCC@4)") (class "Default")
      (node (ref "IC3") (pin "VCC@4") (pinfunction "VCC_VCC@4") (pintype "bidirectional"))
    )
    (net (code "64") (name "unconnected-(IC3-VCC-PadVCC@5)") (class "Default")
      (node (ref "IC3") (pin "VCC@5") (pinfunction "VCC_VCC@5") (pintype "bidirectional"))
    )
    (net (code "65") (name "unconnected-(JP1-Pad5)") (class "Default")
      (node (ref "JP1") (pin "5") (pinfunction "5_5") (pintype "passive"))
    )
    (net (code "66") (name "unconnected-(JP1-Pad7)") (class "Default")
      (node (ref "JP1") (pin "7") (pinfunction "7_7") (pintype "passive"))
    )
    (net (code "67") (name "unconnected-(JP1-Pad9)") (class "Default")
      (node (ref "JP1") (pin "9") (pinfunction "9_9") (pintype "passive"))
    )
    (net (code "68") (name "unconnected-(JP1-Pad11)") (class "Default")
      (node (ref "JP1") (pin "11") (pinfunction "11_11") (pintype "passive"))
    )
    (net (code "69") (name "unconnected-(JP1-Pad13)") (class "Default")
      (node (ref "JP1") (pin "13") (pinfunction "13_13") (pintype "passive"))
    )
    (net (code "70") (name "unconnected-(JP1-Pad15)") (class "Default")
      (node (ref "JP1") (pin "15") (pinfunction "15_15") (pintype "passive"))
    )
  )
)
